# power.net
KiCad netlist of a schematic drawn in Altium Designer
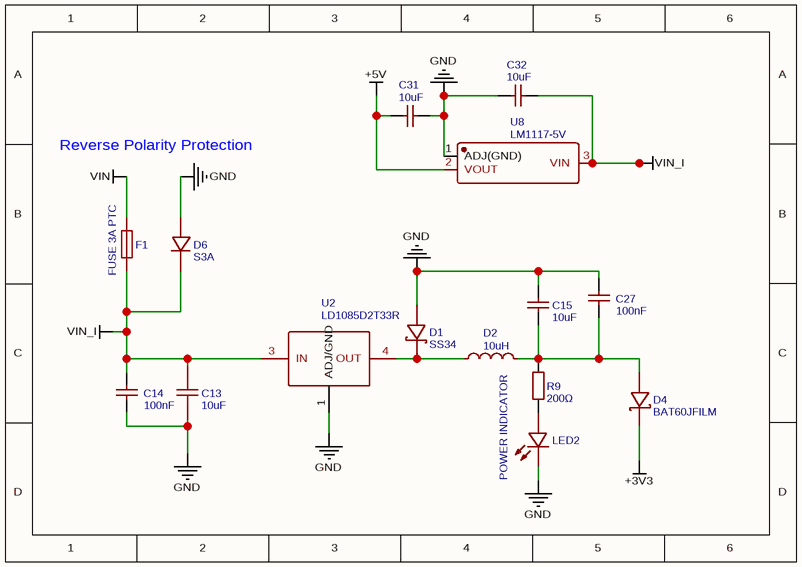
[diagram p0: power.schdoc]

(export (version "E")
  (design (tool "Eeschema 10.0.6"))
  (components
    (comp (ref "C13")
      (value "10uF")
      (fields
        (field (name "MANUFACTURER") "SAMSUNG(三星)")
        (field (name "MANUFACTURER PART") "CL10A106MA8NRNC")
      )
      (libsource (lib "altium-import") (part "root_3_10uF_"))
    )
    (comp (ref "C14")
      (value "100nF")
      (fields
        (field (name "MANUFACTURER PART") "CL05B104KO5NNNC")
        (field (name "MANUFACTURER") "SAMSUNG(三星)")
      )
      (libsource (lib "altium-import") (part "root_3_100nF_"))
    )
    (comp (ref "C15")
      (value "10uF")
      (fields
        (field (name "MANUFACTURER PART") "CL05A106MQ5NUNC")
        (field (name "MANUFACTURER") "SAMSUNG(三星)")
      )
      (libsource (lib "") (part "root_3_10uF__1"))
    )
    (comp (ref "C27")
      (value "100nF")
      (fields
        (field (name "MANUFACTURER PART") "CL05B104KO5NNNC")
        (field (name "MANUFACTURER") "SAMSUNG(三星)")
      )
      (libsource (lib "altium-import") (part "root_3_100nF_"))
    )
    (comp (ref "C31")
      (value "10uF")
      (fields
        (field (name "MANUFACTURER PART") "CL05A106MQ5NUNC")
        (field (name "MANUFACTURER") "SAMSUNG(三星)")
      )
      (libsource (lib "altium-import") (part "root_2_10uF_"))
    )
    (comp (ref "C32")
      (value "10uF")
      (fields
        (field (name "MANUFACTURER PART") "CL05A106MQ5NUNC")
        (field (name "MANUFACTURER") "SAMSUNG(三星)")
      )
      (libsource (lib "altium-import") (part "root_2_10uF_"))
    )
    (comp (ref "D1")
      (value "SS34")
      (fields (field (name "MANUFACTURER PART") "SS34C") (field (name "MANUFACTURER") "MDD"))
      (libsource (lib "altium-import") (part "root_1_SS34_"))
    )
    (comp (ref "D2")
      (value "10uH")
      (fields
        (field (name "MANUFACTURER") "BOURNS")
        (field (name "MANUFACTURER PART") "SRR1280-150M")
        (field (name "CONTRIBUTOR") "LCSC")
      )
      (libsource (lib "altium-import") (part "root_0_10uH_"))
    )
    (comp (ref "D4")
      (value "BAT60JFILM")
      (fields (field (name "MANUFACTURER") "ST(意法半导体)") (field (name "CONTRIBUTOR") "LCSC"))
      (libsource (lib "altium-import") (part "root_1_BAT60JFILM_"))
    )
    (comp (ref "D6")
      (value "S3A")
      (fields (field (name "MANUFACTURER") "LGE(鲁光)") (field (name "CONTRIBUTOR") "LCSC"))
      (libsource (lib "altium-import") (part "root_1_S3A_"))
    )
    (comp (ref "F1")
      (value "FUSE 3A PTC")
      (fields (field (name "MANUFACTURER") "台湾陆海") (field (name "MANUFACTURER PART") "SL1210380"))
      (libsource (lib "altium-import") (part "root_1_FUSE 3A PTC_"))
    )
    (comp (ref "LED2")
      (value "POWER INDICATOR")
      (fields (field (name "MANUFACTURER") "KENTO") (field (name "MANUFACTURER PART") "KT-0603R"))
      (libsource (lib "altium-import") (part "root_1_POWER INDICATOR_"))
    )
    (comp (ref "R9")
      (value "200Ω")
      (fields
        (field (name "MANUFACTURER") "UNI-ROYAL(厚声)")
        (field (name "MANUFACTURER PART") "0402WGF2000TCE")
      )
      (libsource (lib "altium-import") (part "root_3_200Ω_"))
    )
    (comp (ref "U2")
      (value "LD1085D2T33R")
      (fields (field (name "MANUFACTURER") "ST(意法半导体)"))
      (libsource (lib "altium-import") (part "root_0_LD1085D2T33R_"))
    )
    (comp (ref "U8")
      (value "LM1117-5V")
      (fields (field (name "CONTRIBUTOR") "lcsc"))
      (libsource (lib "altium-import") (part "root_0_LM1117-5V_"))
    )
  )
  (nets
    (net (code "1") (name "+3V3") (class "Default")
      (node (ref "D4") (pin "1") (pinfunction "K_1") (pintype "passive"))
    )
    (net (code "2") (name "+5V") (class "Default")
      (node (ref "C31") (pin "2") (pinfunction "2_2") (pintype "passive"))
      (node (ref "U8") (pin "2") (pinfunction "VOUT_2") (pintype "passive"))
    )
    (net (code "3") (name "GND") (class "Default")
      (node (ref "C13") (pin "2") (pinfunction "2_2") (pintype "passive"))
      (node (ref "C14") (pin "1") (pinfunction "1_1") (pintype "passive"))
      (node (ref "C15") (pin "1") (pinfunction "1_1") (pintype "passive"))
      (node (ref "C27") (pin "2") (pinfunction "2_2") (pintype "passive"))
      (node (ref "C31") (pin "1") (pinfunction "1_1") (pintype "passive"))
      (node (ref "C32") (pin "2") (pinfunction "2_2") (pintype "passive"))
      (node (ref "D1") (pin "1") (pinfunction "A_1") (pintype "passive"))
      (node (ref "D6") (pin "2") (pinfunction "2_2") (pintype "passive"))
      (node (ref "LED2") (pin "1") (pinfunction "K_1") (pintype "passive"))
      (node (ref "U2") (pin "1") (pinfunction "ADJ/GND_1") (pintype "passive"))
      (node (ref "U8") (pin "1") (pinfunction "ADJ(GND)_1") (pintype "passive"))
    )
    (net (code "4") (name "Net-(D1-K)") (class "Default")
      (node (ref "D1") (pin "2") (pinfunction "K_2") (pintype "passive"))
      (node (ref "D2") (pin "1") (pinfunction "1_1") (pintype "passive"))
      (node (ref "U2") (pin "4") (pinfunction "OUT_4") (pintype "passive"))
    )
    (net (code "5") (name "Net-(D4-A)") (class "Default")
      (node (ref "C15") (pin "2") (pinfunction "2_2") (pintype "passive"))
      (node (ref "C27") (pin "1") (pinfunction "1_1") (pintype "passive"))
      (node (ref "D2") (pin "2") (pinfunction "2_2") (pintype "passive"))
      (node (ref "D4") (pin "2") (pinfunction "A_2") (pintype "passive"))
      (node (ref "R9") (pin "1") (pinfunction "1_1") (pintype "passive"))
    )
    (net (code "6") (name "Net-(LED2-A)") (class "Default")
      (node (ref "LED2") (pin "2") (pinfunction "A_2") (pintype "passive"))
      (node (ref "R9") (pin "2") (pinfunction "2_2") (pintype "passive"))
    )
    (net (code "7") (name "VIN") (class "Default")
      (node (ref "F1") (pin "2") (pinfunction "2_2") (pintype "passive"))
    )
    (net (code "8") (name "VIN_I") (class "Default")
      (node (ref "C13") (pin "1") (pinfunction "1_1") (pintype "passive"))
      (node (ref "C14") (pin "2") (pinfunction "2_2") (pintype "passive"))
      (node (ref "C32") (pin "1") (pinfunction "1_1") (pintype "passive"))
      (node (ref "D6") (pin "1") (pinfunction "1_1") (pintype "passive"))
      (node (ref "F1") (pin "1") (pinfunction "1_1") (pintype "passive"))
      (node (ref "U2") (pin "3") (pinfunction "IN_3") (pintype "passive"))
      (node (ref "U8") (pin "3") (pinfunction "VIN_3") (pintype "passive"))
    )
  )
)
